# Band_Pass.net
KiCad netlist of a schematic drawn in Altium Designer
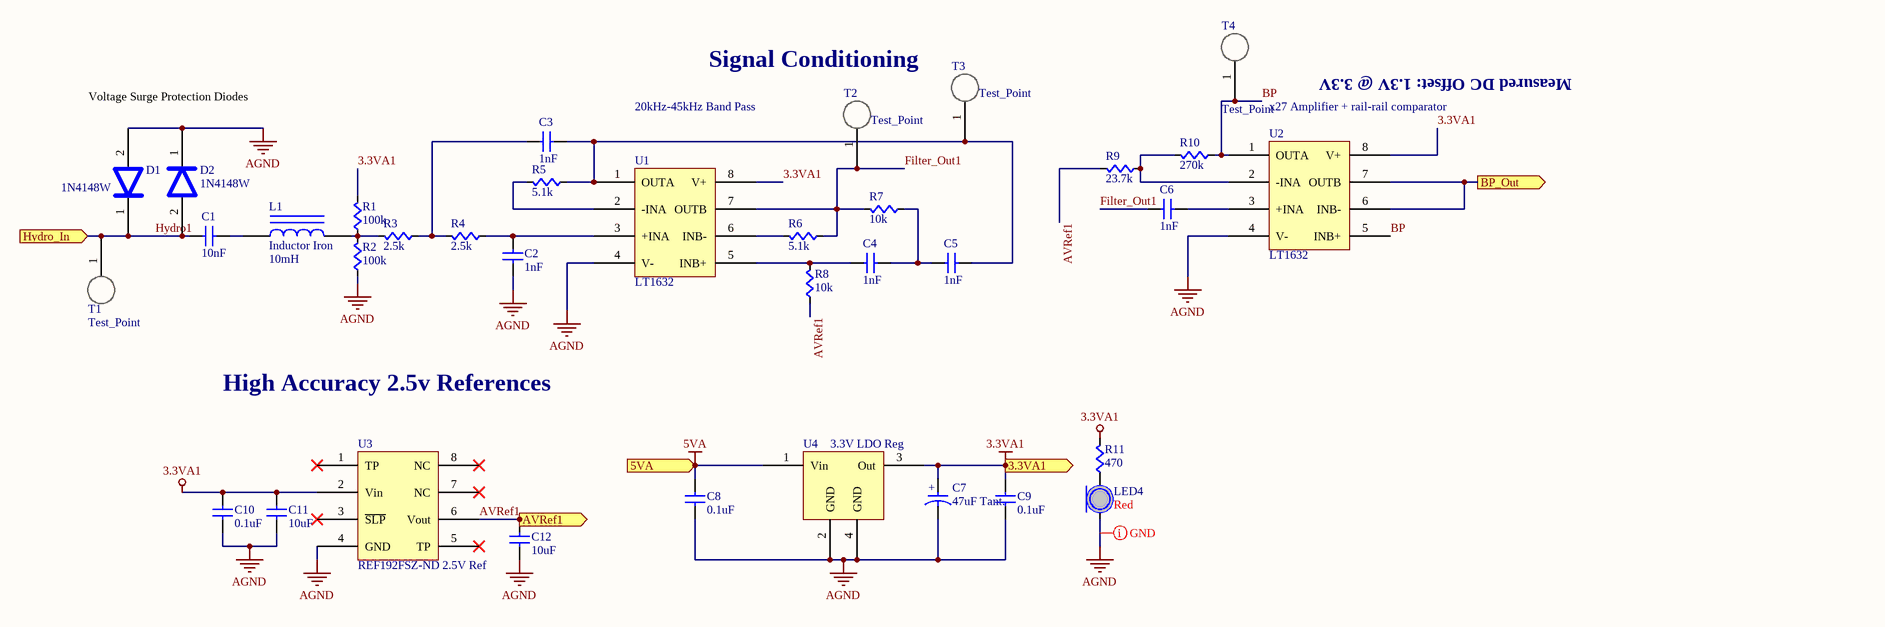
[diagram p0: Band_Pass.SchDoc]

(export (version "E")
  (design (tool "Eeschema 10.0.6"))
  (components
    (comp (ref "C1")
      (value "10nF")
      (footprint "CAPC0603")
      (fields (field (name "Comment") "Cap"))
      (libsource (lib "SubjuGator8") (part "Cap"))
    )
    (comp (ref "C2")
      (value "1nF")
      (footprint "CAPC0603")
      (fields (field (name "Comment") "Cap"))
      (libsource (lib "SubjuGator8") (part "Cap"))
    )
    (comp (ref "C3")
      (value "1nF")
      (footprint "CAPC0603")
      (fields (field (name "Comment") "Cap"))
      (libsource (lib "SubjuGator8") (part "Cap"))
    )
    (comp (ref "C4")
      (value "1nF")
      (footprint "CAPC0603")
      (fields (field (name "Comment") "Cap"))
      (libsource (lib "SubjuGator8") (part "Cap"))
    )
    (comp (ref "C5")
      (value "1nF")
      (footprint "CAPC0603")
      (fields (field (name "Comment") "Cap"))
      (libsource (lib "SubjuGator8") (part "Cap"))
    )
    (comp (ref "C6")
      (value "1nF")
      (footprint "CAPC0603")
      (fields (field (name "Comment") "Cap"))
      (libsource (lib "SubjuGator8") (part "Cap"))
    )
    (comp (ref "C7")
      (value "47uF Tant.")
      (footprint "1206")
      (description "CAP TANT 47UF 10V 10% 1411")
      (fields (field (name "Comment") "Cap Tant"))
      (libsource (lib "Passives") (part "CapPol"))
    )
    (comp (ref "C8")
      (value "0.1uF")
      (footprint "CAPC0603")
      (fields (field (name "Comment") "Cap"))
      (libsource (lib "SubjuGator8") (part "Cap"))
    )
    (comp (ref "C9")
      (value "0.1uF")
      (footprint "CAPC0603")
      (fields (field (name "Comment") "Cap"))
      (libsource (lib "SubjuGator8") (part "Cap"))
    )
    (comp (ref "C10")
      (value "0.1uF")
      (footprint "CAPC0603")
      (fields (field (name "Comment") "Cap"))
      (libsource (lib "SubjuGator8") (part "Cap"))
    )
    (comp (ref "C11")
      (value "10uF")
      (footprint "CAPC0603")
      (fields (field (name "Comment") "Cap"))
      (libsource (lib "SubjuGator8") (part "Cap"))
    )
    (comp (ref "C12")
      (value "10uF")
      (footprint "CAPC0603")
      (fields (field (name "Comment") "Cap"))
      (libsource (lib "SubjuGator8") (part "Cap"))
    )
    (comp (ref "D1")
      (value "1N4148W")
      (footprint "SOD-123")
      (description "DIODE GEN PURP 75V 150MA SOD123")
      (libsource (lib "Miscellaneous Devices") (part "1N4148W"))
    )
    (comp (ref "D2")
      (value "1N4148W")
      (footprint "SOD-123")
      (description "DIODE GEN PURP 75V 150MA SOD123")
      (libsource (lib "Miscellaneous Devices") (part "1N4148W"))
    )
    (comp (ref "L1")
      (value "Inductor Iron")
      (footprint "Axial-11.7")
      (description "Magnetic-Core Inductor")
      (fields (field (name "ALTIUM_VALUE") "10mH") (field (name "PUBLISHER") "Altium Limited"))
      (libsource (lib "Miscellaneous Devices") (part "Inductor Iron"))
    )
    (comp (ref "LED4")
      (value "LED")
      (footprint "LED0805")
      (fields (field (name "COLOR") "Red"))
      (libsource (lib "Semiconductors") (part "LED"))
    )
    (comp (ref "R1")
      (value "100k")
      (footprint "RES0603")
      (fields (field (name "Comment") "Res"))
      (libsource (lib "Passives") (part "Res"))
    )
    (comp (ref "R2")
      (value "100k")
      (footprint "RES0603")
      (fields (field (name "Comment") "Res"))
      (libsource (lib "Passives") (part "Res"))
    )
    (comp (ref "R3")
      (value "2.5k")
      (footprint "RES0603")
      (fields (field (name "Comment") "Res"))
      (libsource (lib "Passives") (part "Res"))
    )
    (comp (ref "R4")
      (value "2.5k")
      (footprint "RES0603")
      (fields (field (name "Comment") "Res"))
      (libsource (lib "Passives") (part "Res"))
    )
    (comp (ref "R5")
      (value "5.1k")
      (footprint "RES0603")
      (fields (field (name "Comment") "Res"))
      (libsource (lib "Passives") (part "Res"))
    )
    (comp (ref "R6")
      (value "5.1k")
      (footprint "RES0603")
      (fields (field (name "Comment") "Res"))
      (libsource (lib "Passives") (part "Res"))
    )
    (comp (ref "R7")
      (value "10k")
      (footprint "RES0603")
      (fields (field (name "Comment") "Res"))
      (libsource (lib "Passives") (part "Res"))
    )
    (comp (ref "R8")
      (value "10k")
      (footprint "RES0603")
      (fields (field (name "Comment") "Res"))
      (libsource (lib "Passives") (part "Res"))
    )
    (comp (ref "R9")
      (value "23.7k")
      (footprint "RES0603")
      (fields (field (name "Comment") "Res"))
      (libsource (lib "Passives") (part "Res"))
    )
    (comp (ref "R10")
      (value "270k")
      (footprint "RES0603")
      (fields (field (name "Comment") "Res"))
      (libsource (lib "Passives") (part "Res"))
    )
    (comp (ref "R11")
      (value "470")
      (footprint "RES0603")
      (fields (field (name "Comment") "Res"))
      (libsource (lib "Passives") (part "Res"))
    )
    (comp (ref "T1")
      (value "Test_Point")
      (footprint "TP")
      (description "TEST POINT PC COMPACT .063\"D")
      (libsource (lib "Hydrophone") (part "Test_Point"))
    )
    (comp (ref "T2")
      (value "Test_Point")
      (footprint "TP")
      (description "TEST POINT PC COMPACT .063\"D")
      (libsource (lib "Hydrophone") (part "Test_Point"))
    )
    (comp (ref "T3")
      (value "Test_Point")
      (footprint "TP")
      (description "TEST POINT PC COMPACT .063\"D")
      (libsource (lib "Hydrophone") (part "Test_Point"))
    )
    (comp (ref "T4")
      (value "Test_Point")
      (footprint "TP")
      (description "TEST POINT PC COMPACT .063\"D")
      (libsource (lib "Hydrophone") (part "Test_Point"))
    )
    (comp (ref "U1")
      (value "LT1632")
      (footprint "SOIC127P600-8N")
      (description "IC OPAMP GP 45MHZ RRO 8SO")
      (libsource (lib "SubjuGator8") (part "LT1632"))
    )
    (comp (ref "U2")
      (value "LT1632")
      (footprint "SOIC127P600-8N")
      (description "IC OPAMP GP 45MHZ RRO 8SO")
      (libsource (lib "SubjuGator8") (part "LT1632"))
    )
    (comp (ref "U3")
      (value "REF192FSZ-ND 2.5V Ref")
      (footprint "SOIC2.5-8n")
      (description "IC VREF SERIES 2.5V 8SOIC")
      (libsource (lib "SubjuGator8") (part "Ref2.5V"))
    )
    (comp (ref "U4")
      (value "3.3V LDO Reg")
      (footprint "SOT23-4n")
      (description "IC REG LDO 3.3V 1A SOT223")
      (libsource (lib "SubjuGator8") (part "LM3940IMPX-3.3"))
    )
  )
  (nets
    (net (code "1") (name "/AVRef1") (class "Default")
      (node (ref "C12") (pin "1") (pinfunction "A_1") (pintype "passive"))
      (node (ref "R8") (pin "2") (pinfunction "B_2") (pintype "passive"))
      (node (ref "R9") (pin "1") (pinfunction "A_1") (pintype "passive"))
      (node (ref "U3") (pin "6") (pinfunction "Vout_6") (pintype "passive"))
    )
    (net (code "2") (name "/BP") (class "Default")
      (node (ref "R10") (pin "2") (pinfunction "B_2") (pintype "passive"))
      (node (ref "T4") (pin "1") (pintype "passive"))
      (node (ref "U2") (pin "1") (pinfunction "OUTA_1") (pintype "passive"))
      (node (ref "U2") (pin "5") (pinfunction "INB+_5") (pintype "passive"))
    )
    (net (code "3") (name "/BP_Out") (class "Default")
      (node (ref "U2") (pin "6") (pinfunction "INB-_6") (pintype "passive"))
      (node (ref "U2") (pin "7") (pinfunction "OUTB_7") (pintype "passive"))
    )
    (net (code "4") (name "/Filter_Out1") (class "Default")
      (node (ref "C6") (pin "1") (pinfunction "A_1") (pintype "passive"))
      (node (ref "R6") (pin "2") (pinfunction "B_2") (pintype "passive"))
      (node (ref "R7") (pin "1") (pinfunction "A_1") (pintype "passive"))
      (node (ref "T2") (pin "1") (pintype "passive"))
      (node (ref "U1") (pin "7") (pinfunction "OUTB_7") (pintype "passive"))
    )
    (net (code "5") (name "/Hydro1") (class "Default")
      (node (ref "C1") (pin "1") (pinfunction "A_1") (pintype "passive"))
      (node (ref "D1") (pin "1") (pintype "passive"))
      (node (ref "D2") (pin "2") (pintype "passive"))
      (node (ref "T1") (pin "1") (pintype "passive"))
    )
    (net (code "6") (name "3.3VA1") (class "Default")
      (node (ref "C10") (pin "1") (pinfunction "A_1") (pintype "passive"))
      (node (ref "C11") (pin "1") (pinfunction "A_1") (pintype "passive"))
      (node (ref "C7") (pin "1") (pinfunction "A_1") (pintype "passive"))
      (node (ref "C9") (pin "1") (pinfunction "A_1") (pintype "passive"))
      (node (ref "R1") (pin "1") (pinfunction "A_1") (pintype "passive"))
      (node (ref "R11") (pin "1") (pinfunction "A_1") (pintype "passive"))
      (node (ref "U1") (pin "8") (pinfunction "V+_8") (pintype "passive"))
      (node (ref "U2") (pin "8") (pinfunction "V+_8") (pintype "passive"))
      (node (ref "U3") (pin "2") (pinfunction "Vin_2") (pintype "passive"))
      (node (ref "U4") (pin "3") (pinfunction "Out_3") (pintype "passive"))
    )
    (net (code "7") (name "5VA") (class "Default")
      (node (ref "C8") (pin "1") (pinfunction "A_1") (pintype "passive"))
      (node (ref "U4") (pin "1") (pinfunction "Vin_1") (pintype "passive"))
    )
    (net (code "8") (name "AGND") (class "Default")
      (node (ref "C10") (pin "2") (pinfunction "B_2") (pintype "passive"))
      (node (ref "C11") (pin "2") (pinfunction "B_2") (pintype "passive"))
      (node (ref "C12") (pin "2") (pinfunction "B_2") (pintype "passive"))
      (node (ref "C2") (pin "2") (pinfunction "B_2") (pintype "passive"))
      (node (ref "C7") (pin "2") (pinfunction "B_2") (pintype "passive"))
      (node (ref "C8") (pin "2") (pinfunction "B_2") (pintype "passive"))
      (node (ref "C9") (pin "2") (pinfunction "B_2") (pintype "passive"))
      (node (ref "D1") (pin "2") (pintype "passive"))
      (node (ref "D2") (pin "1") (pintype "passive"))
      (node (ref "LED4") (pin "C") (pinfunction "C_C") (pintype "passive"))
      (node (ref "R2") (pin "2") (pinfunction "B_2") (pintype "passive"))
      (node (ref "U1") (pin "4") (pinfunction "V-_4") (pintype "passive"))
      (node (ref "U2") (pin "4") (pinfunction "V-_4") (pintype "passive"))
      (node (ref "U3") (pin "4") (pinfunction "GND_4") (pintype "passive"))
      (node (ref "U4") (pin "2") (pinfunction "GND_2") (pintype "passive"))
      (node (ref "U4") (pin "4") (pinfunction "GND_4") (pintype "passive"))
    )
    (net (code "9") (name "Net-(C1-B)") (class "Default")
      (node (ref "C1") (pin "2") (pinfunction "B_2") (pintype "passive"))
      (node (ref "L1") (pin "1") (pinfunction "1_1") (pintype "passive"))
    )
    (net (code "10") (name "Net-(C2-A)") (class "Default")
      (node (ref "C2") (pin "1") (pinfunction "A_1") (pintype "passive"))
      (node (ref "R4") (pin "2") (pinfunction "B_2") (pintype "passive"))
      (node (ref "U1") (pin "3") (pinfunction "+INA_3") (pintype "passive"))
    )
    (net (code "11") (name "Net-(C3-A)") (class "Default")
      (node (ref "C3") (pin "1") (pinfunction "A_1") (pintype "passive"))
      (node (ref "R3") (pin "2") (pinfunction "B_2") (pintype "passive"))
      (node (ref "R4") (pin "1") (pinfunction "A_1") (pintype "passive"))
    )
    (net (code "12") (name "Net-(C3-B)") (class "Default")
      (node (ref "C3") (pin "2") (pinfunction "B_2") (pintype "passive"))
      (node (ref "C5") (pin "2") (pinfunction "B_2") (pintype "passive"))
      (node (ref "R5") (pin "2") (pinfunction "B_2") (pintype "passive"))
      (node (ref "T3") (pin "1") (pintype "passive"))
      (node (ref "U1") (pin "1") (pinfunction "OUTA_1") (pintype "passive"))
    )
    (net (code "13") (name "Net-(C4-A)") (class "Default")
      (node (ref "C4") (pin "1") (pinfunction "A_1") (pintype "passive"))
      (node (ref "R8") (pin "1") (pinfunction "A_1") (pintype "passive"))
      (node (ref "U1") (pin "5") (pinfunction "INB+_5") (pintype "passive"))
    )
    (net (code "14") (name "Net-(C4-B)") (class "Default")
      (node (ref "C4") (pin "2") (pinfunction "B_2") (pintype "passive"))
      (node (ref "C5") (pin "1") (pinfunction "A_1") (pintype "passive"))
      (node (ref "R7") (pin "2") (pinfunction "B_2") (pintype "passive"))
    )
    (net (code "15") (name "Net-(C6-B)") (class "Default")
      (node (ref "C6") (pin "2") (pinfunction "B_2") (pintype "passive"))
      (node (ref "U2") (pin "3") (pinfunction "+INA_3") (pintype "passive"))
    )
    (net (code "16") (name "Net-(R1-B)") (class "Default")
      (node (ref "L1") (pin "2") (pinfunction "2_2") (pintype "passive"))
      (node (ref "R1") (pin "2") (pinfunction "B_2") (pintype "passive"))
      (node (ref "R2") (pin "1") (pinfunction "A_1") (pintype "passive"))
      (node (ref "R3") (pin "1") (pinfunction "A_1") (pintype "passive"))
    )
    (net (code "17") (name "Net-(R5-A)") (class "Default")
      (node (ref "R5") (pin "1") (pinfunction "A_1") (pintype "passive"))
      (node (ref "U1") (pin "2") (pinfunction "-INA_2") (pintype "passive"))
    )
    (net (code "18") (name "Net-(R6-A)") (class "Default")
      (node (ref "R6") (pin "1") (pinfunction "A_1") (pintype "passive"))
      (node (ref "U1") (pin "6") (pinfunction "INB-_6") (pintype "passive"))
    )
    (net (code "19") (name "Net-(R10-A)") (class "Default")
      (node (ref "R10") (pin "1") (pinfunction "A_1") (pintype "passive"))
      (node (ref "R9") (pin "2") (pinfunction "B_2") (pintype "passive"))
      (node (ref "U2") (pin "2") (pinfunction "-INA_2") (pintype "passive"))
    )
    (net (code "20") (name "Net-(R11-B)") (class "Default")
      (node (ref "LED4") (pin "A") (pinfunction "A_A") (pintype "passive"))
      (node (ref "R11") (pin "2") (pinfunction "B_2") (pintype "passive"))
    )
    (net (code "21") (name "unconnected-(U3-NC-Pad7)") (class "Default")
      (node (ref "U3") (pin "7") (pinfunction "NC_7") (pintype "passive+no_connect"))
    )
    (net (code "22") (name "unconnected-(U3-NC-Pad8)") (class "Default")
      (node (ref "U3") (pin "8") (pinfunction "NC_8") (pintype "passive+no_connect"))
    )
    (net (code "23") (name "unconnected-(U3-TP-Pad1)") (class "Default")
      (node (ref "U3") (pin "1") (pinfunction "TP_1") (pintype "passive+no_connect"))
    )
    (net (code "24") (name "unconnected-(U3-TP-Pad5)") (class "Default")
      (node (ref "U3") (pin "5") (pinfunction "TP_5") (pintype "passive+no_connect"))
    )
    (net (code "25") (name "unconnected-(U3-~{SLP}-Pad3)") (class "Default")
      (node (ref "U3") (pin "3") (pinfunction "~{SLP}_3") (pintype "passive+no_connect"))
    )
  )
)
